# cpu.net
KiCad netlist of a schematic drawn in Altium Designer
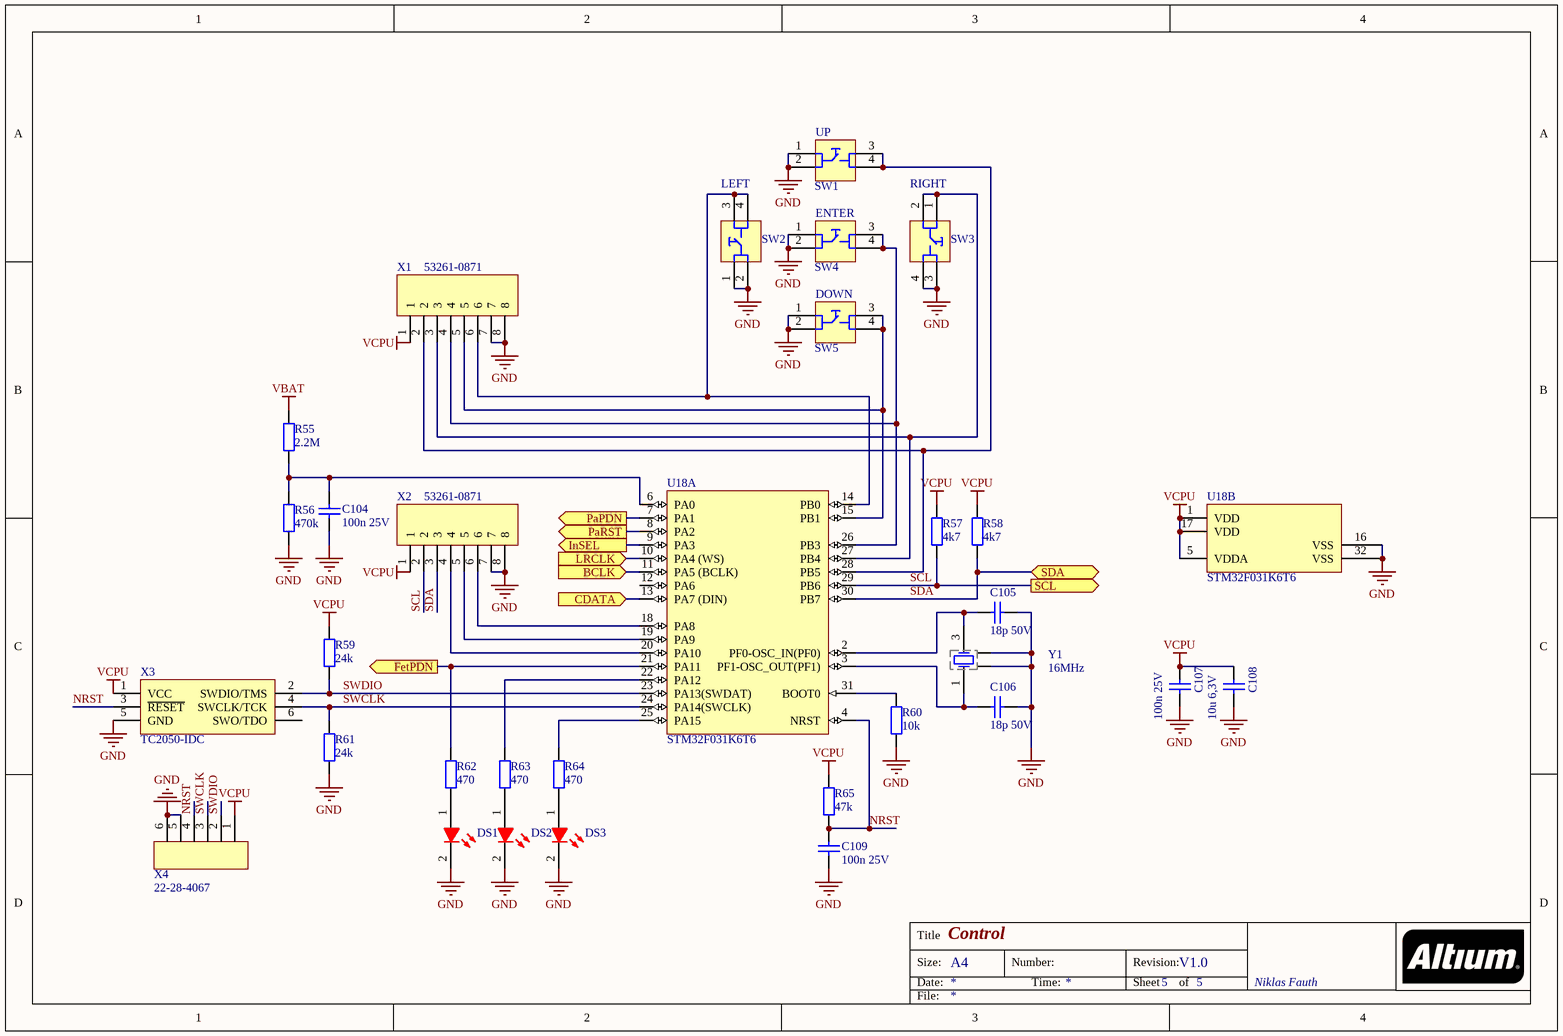
[diagram p0: cpu.SchDoc]

(export (version "E")
  (design (tool "Eeschema 10.0.6"))
  (components
    (comp (ref "C104")
      (value "100n 25V")
      (footprint "C-0603-H")
      (description "Capacitor 100n 25V")
      (libsource (lib "Passives") (part "C-0603-100n-25V"))
    )
    (comp (ref "C105")
      (value "18p 50V")
      (footprint "C-0402-M")
      (description "Capacitor 18p 50V")
      (libsource (lib "Passives") (part "C-0402-18p-50V"))
    )
    (comp (ref "C106")
      (value "18p 50V")
      (footprint "C-0402-M")
      (description "Capacitor 18p 50V")
      (libsource (lib "Passives") (part "C-0402-18p-50V"))
    )
    (comp (ref "C107")
      (value "100n 25V")
      (footprint "C-0603-H")
      (description "Capacitor 100n 25V")
      (libsource (lib "Passives") (part "C-0603-100n-25V"))
    )
    (comp (ref "C108")
      (value "10u 6,3V")
      (footprint "C-0603-H")
      (description "Capacitor 10uF 6,3V")
      (libsource (lib "Passives") (part "C-0603-10u-6,3V"))
    )
    (comp (ref "C109")
      (value "100n 25V")
      (footprint "C-0603-H")
      (description "Capacitor 100n 25V")
      (libsource (lib "Passives") (part "C-0603-100n-25V"))
    )
    (comp (ref "DS1")
      (value "LED-0603-RED")
      (footprint "LED-0603-RED")
      (libsource (lib "advanced") (part "LED-0603-RED"))
    )
    (comp (ref "DS2")
      (value "LED-0603-RED")
      (footprint "LED-0603-RED")
      (libsource (lib "advanced") (part "LED-0603-RED"))
    )
    (comp (ref "DS3")
      (value "LED-0603-RED")
      (footprint "LED-0603-RED")
      (libsource (lib "advanced") (part "LED-0603-RED"))
    )
    (comp (ref "R55")
      (value "2.2M")
      (footprint "R-0603-H")
      (description "Resistor 2.2M")
      (libsource (lib "Passives") (part "R-0603-2M2"))
    )
    (comp (ref "R56")
      (value "470k")
      (footprint "R-0603-H")
      (description "Resistor 470k")
      (libsource (lib "Passives") (part "R-0603-470k"))
    )
    (comp (ref "R57")
      (value "4k7")
      (footprint "R-0603-H")
      (description "Resistor 4k7")
      (libsource (lib "Passives") (part "R-0603-4k7"))
    )
    (comp (ref "R58")
      (value "4k7")
      (footprint "R-0603-H")
      (description "Resistor 4k7")
      (libsource (lib "Passives") (part "R-0603-4k7"))
    )
    (comp (ref "R59")
      (value "24k")
      (footprint "R-0402-M")
      (description "Resistor 24k")
      (libsource (lib "Passives") (part "R-0402-24k"))
    )
    (comp (ref "R60")
      (value "10k")
      (footprint "R-0603-H")
      (description "Resistor 10k")
      (libsource (lib "Passives") (part "R-0603-10k"))
    )
    (comp (ref "R61")
      (value "24k")
      (footprint "R-0402-M")
      (description "Resistor 24k")
      (libsource (lib "Passives") (part "R-0402-24k"))
    )
    (comp (ref "R62")
      (value "470")
      (footprint "R-0603-H")
      (description "Resistor 470")
      (libsource (lib "Passives") (part "R-0603-470"))
    )
    (comp (ref "R63")
      (value "470")
      (footprint "R-0603-H")
      (description "Resistor 470")
      (libsource (lib "Passives") (part "R-0603-470"))
    )
    (comp (ref "R64")
      (value "470")
      (footprint "R-0603-H")
      (description "Resistor 470")
      (libsource (lib "Passives") (part "R-0603-470"))
    )
    (comp (ref "R65")
      (value "47k")
      (footprint "R-0603-H")
      (description "Resistor 4k7")
      (libsource (lib "Passives") (part "R-0603-47k"))
    )
    (comp (ref "SW1") (value "UP") (footprint "BUTTON_TACT") (libsource (lib "") (part "SWITCH-TACTILE_1")))
    (comp (ref "SW2")
      (value "LEFT")
      (footprint "BUTTON_TACT")
      (libsource (lib "advanced") (part "SWITCH-TACTILE"))
    )
    (comp (ref "SW3")
      (value "RIGHT")
      (footprint "BUTTON_TACT")
      (libsource (lib "") (part "SWITCH-TACTILE_2"))
    )
    (comp (ref "SW4")
      (value "ENTER")
      (footprint "BUTTON_TACT")
      (libsource (lib "") (part "SWITCH-TACTILE_1"))
    )
    (comp (ref "SW5") (value "DOWN") (footprint "BUTTON_TACT") (libsource (lib "") (part "SWITCH-TACTILE_1")))
    (comp (ref "U18")
      (value "STM32F031K6T6")
      (footprint "LQFP32")
      (libsource (lib "advanced") (part "STM32F031K6T6"))
    )
    (comp (ref "X1")
      (value "53261-0871")
      (footprint "mlx-picoBlade-8p-right-SMD")
      (libsource (lib "advanced") (part "MLX-picoBlade-8P-right-SMD"))
    )
    (comp (ref "X2")
      (value "53261-0871")
      (footprint "mlx-picoBlade-8p-right-SMD")
      (libsource (lib "advanced") (part "MLX-picoBlade-8P-right-SMD"))
    )
    (comp (ref "X3")
      (value "TC2050-IDC")
      (footprint "TC2030-IDC")
      (description "TC2050-IDC SWD")
      (libsource (lib "advanced") (part "TAG-Connect-SWD"))
    )
    (comp (ref "X4")
      (value "22-28-4067")
      (footprint "PINHEAD-MALE-6")
      (libsource (lib "advanced") (part "PINHEAD-MALE-6"))
    )
    (comp (ref "Y1") (value "16MHz") (footprint "ABM10") (libsource (lib "advanced") (part "ABM10-16MHz")))
  )
  (nets
    (net (code "1") (name "/BCLK") (class "Default")
      (node (ref "U18") (pin "11") (pinfunction "PA5_(BCLK)_11") (pintype "bidirectional"))
    )
    (net (code "2") (name "/CDATA") (class "Default")
      (node (ref "U18") (pin "13") (pinfunction "PA7_(DIN)_13") (pintype "bidirectional"))
    )
    (net (code "3") (name "/FetPDN") (class "Default")
      (node (ref "R62") (pin "2") (pinfunction "2_2") (pintype "passive"))
      (node (ref "U18") (pin "21") (pinfunction "PA11_21") (pintype "bidirectional"))
    )
    (net (code "4") (name "/InSEL") (class "Default")
      (node (ref "U18") (pin "9") (pinfunction "PA3_9") (pintype "bidirectional"))
    )
    (net (code "5") (name "/LRCLK") (class "Default")
      (node (ref "U18") (pin "10") (pinfunction "PA4_(WS)_10") (pintype "bidirectional"))
    )
    (net (code "6") (name "/NRST") (class "Default")
      (node (ref "C109") (pin "2") (pinfunction "2_2") (pintype "passive"))
      (node (ref "R65") (pin "1") (pinfunction "1_1") (pintype "passive"))
      (node (ref "U18") (pin "4") (pinfunction "NRST_4") (pintype "bidirectional"))
      (node (ref "X3") (pin "3") (pinfunction "~{RESET}_3") (pintype "passive"))
      (node (ref "X4") (pin "4") (pintype "passive"))
    )
    (net (code "7") (name "/PaPDN") (class "Default")
      (node (ref "U18") (pin "7") (pinfunction "PA1_7") (pintype "bidirectional"))
    )
    (net (code "8") (name "/PaRST") (class "Default")
      (node (ref "U18") (pin "8") (pinfunction "PA2_8") (pintype "bidirectional"))
    )
    (net (code "9") (name "/SCL") (class "Default")
      (node (ref "R57") (pin "1") (pinfunction "1_1") (pintype "passive"))
      (node (ref "U18") (pin "29") (pinfunction "PB6_29") (pintype "bidirectional"))
      (node (ref "X2") (pin "2") (pinfunction "2_2") (pintype "passive"))
    )
    (net (code "10") (name "/SDA") (class "Default")
      (node (ref "R58") (pin "1") (pinfunction "1_1") (pintype "passive"))
      (node (ref "U18") (pin "30") (pinfunction "PB7_30") (pintype "bidirectional"))
      (node (ref "X2") (pin "3") (pinfunction "3_3") (pintype "passive"))
    )
    (net (code "11") (name "/SWCLK") (class "Default")
      (node (ref "R61") (pin "2") (pinfunction "2_2") (pintype "passive"))
      (node (ref "U18") (pin "24") (pinfunction "PA14(SWCLK)_24") (pintype "bidirectional"))
      (node (ref "X3") (pin "4") (pinfunction "SWCLK/TCK_4") (pintype "passive"))
      (node (ref "X4") (pin "3") (pintype "passive"))
    )
    (net (code "12") (name "/SWDIO") (class "Default")
      (node (ref "R59") (pin "1") (pinfunction "1_1") (pintype "passive"))
      (node (ref "U18") (pin "23") (pinfunction "PA13(SWDAT)_23") (pintype "bidirectional"))
      (node (ref "X3") (pin "2") (pinfunction "SWDIO/TMS_2") (pintype "passive"))
      (node (ref "X4") (pin "2") (pintype "passive"))
    )
    (net (code "13") (name "GND") (class "Default")
      (node (ref "C104") (pin "1") (pinfunction "1_1") (pintype "passive"))
      (node (ref "C105") (pin "2") (pinfunction "2_2") (pintype "passive"))
      (node (ref "C106") (pin "2") (pinfunction "2_2") (pintype "passive"))
      (node (ref "C107") (pin "1") (pinfunction "1_1") (pintype "passive"))
      (node (ref "C108") (pin "1") (pinfunction "1_1") (pintype "passive"))
      (node (ref "C109") (pin "1") (pinfunction "1_1") (pintype "passive"))
      (node (ref "DS1") (pin "2") (pinfunction "K_2") (pintype "passive"))
      (node (ref "DS2") (pin "2") (pinfunction "K_2") (pintype "passive"))
      (node (ref "DS3") (pin "2") (pinfunction "K_2") (pintype "passive"))
      (node (ref "R56") (pin "1") (pinfunction "1_1") (pintype "passive"))
      (node (ref "R60") (pin "1") (pinfunction "1_1") (pintype "passive"))
      (node (ref "R61") (pin "1") (pinfunction "1_1") (pintype "passive"))
      (node (ref "SW1") (pin "1") (pintype "passive"))
      (node (ref "SW1") (pin "2") (pintype "passive"))
      (node (ref "SW2") (pin "1") (pintype "passive"))
      (node (ref "SW2") (pin "2") (pintype "passive"))
      (node (ref "SW3") (pin "3") (pintype "passive"))
      (node (ref "SW3") (pin "4") (pintype "passive"))
      (node (ref "SW4") (pin "1") (pintype "passive"))
      (node (ref "SW4") (pin "2") (pintype "passive"))
      (node (ref "SW5") (pin "1") (pintype "passive"))
      (node (ref "SW5") (pin "2") (pintype "passive"))
      (node (ref "U18") (pin "16") (pinfunction "VSS_16") (pintype "passive"))
      (node (ref "U18") (pin "32") (pinfunction "VSS_32") (pintype "passive"))
      (node (ref "X1") (pin "7") (pinfunction "7_7") (pintype "power_in"))
      (node (ref "X1") (pin "8") (pinfunction "8_8") (pintype "power_in"))
      (node (ref "X2") (pin "7") (pinfunction "7_7") (pintype "power_in"))
      (node (ref "X2") (pin "8") (pinfunction "8_8") (pintype "power_in"))
      (node (ref "X3") (pin "5") (pinfunction "GND_5") (pintype "passive"))
      (node (ref "X4") (pin "5") (pinfunction "5_5") (pintype "passive"))
      (node (ref "X4") (pin "6") (pinfunction "6_6") (pintype "passive"))
      (node (ref "Y1") (pin "2") (pintype "power_in"))
      (node (ref "Y1") (pin "4") (pintype "power_in"))
    )
    (net (code "14") (name "Net-(DS1-A)") (class "Default")
      (node (ref "DS1") (pin "1") (pinfunction "A_1") (pintype "passive"))
      (node (ref "R62") (pin "1") (pinfunction "1_1") (pintype "passive"))
    )
    (net (code "15") (name "Net-(DS2-A)") (class "Default")
      (node (ref "DS2") (pin "1") (pinfunction "A_1") (pintype "passive"))
      (node (ref "R63") (pin "1") (pinfunction "1_1") (pintype "passive"))
    )
    (net (code "16") (name "Net-(DS3-A)") (class "Default")
      (node (ref "DS3") (pin "1") (pinfunction "A_1") (pintype "passive"))
      (node (ref "R64") (pin "1") (pinfunction "1_1") (pintype "passive"))
    )
    (net (code "17") (name "Net-(U18A-BOOT0)") (class "Default")
      (node (ref "R60") (pin "2") (pinfunction "2_2") (pintype "passive"))
      (node (ref "U18") (pin "31") (pinfunction "BOOT0_31") (pintype "input"))
    )
    (net (code "18") (name "Net-(U18A-PA0)") (class "Default")
      (node (ref "C104") (pin "2") (pinfunction "2_2") (pintype "passive"))
      (node (ref "R55") (pin "1") (pinfunction "1_1") (pintype "passive"))
      (node (ref "R56") (pin "2") (pinfunction "2_2") (pintype "passive"))
      (node (ref "U18") (pin "6") (pinfunction "PA0_6") (pintype "bidirectional"))
    )
    (net (code "19") (name "Net-(U18A-PA8)") (class "Default")
      (node (ref "U18") (pin "18") (pinfunction "PA8_18") (pintype "bidirectional"))
      (node (ref "X2") (pin "6") (pinfunction "6_6") (pintype "power_in"))
    )
    (net (code "20") (name "Net-(U18A-PA9)") (class "Default")
      (node (ref "U18") (pin "19") (pinfunction "PA9_19") (pintype "bidirectional"))
      (node (ref "X2") (pin "5") (pinfunction "5_5") (pintype "passive"))
    )
    (net (code "21") (name "Net-(U18A-PA10)") (class "Default")
      (node (ref "U18") (pin "20") (pinfunction "PA10_20") (pintype "bidirectional"))
      (node (ref "X2") (pin "4") (pinfunction "4_4") (pintype "passive"))
    )
    (net (code "22") (name "Net-(U18A-PA12)") (class "Default")
      (node (ref "R63") (pin "2") (pinfunction "2_2") (pintype "passive"))
      (node (ref "U18") (pin "22") (pinfunction "PA12_22") (pintype "bidirectional"))
    )
    (net (code "23") (name "Net-(U18A-PA15)") (class "Default")
      (node (ref "R64") (pin "2") (pinfunction "2_2") (pintype "passive"))
      (node (ref "U18") (pin "25") (pinfunction "PA15_25") (pintype "bidirectional"))
    )
    (net (code "24") (name "Net-(U18A-PB0)") (class "Default")
      (node (ref "SW2") (pin "3") (pintype "passive"))
      (node (ref "SW2") (pin "4") (pintype "passive"))
      (node (ref "U18") (pin "14") (pinfunction "PB0_14") (pintype "bidirectional"))
      (node (ref "X1") (pin "6") (pinfunction "6_6") (pintype "power_in"))
    )
    (net (code "25") (name "Net-(U18A-PB1)") (class "Default")
      (node (ref "SW5") (pin "3") (pintype "passive"))
      (node (ref "SW5") (pin "4") (pintype "passive"))
      (node (ref "U18") (pin "15") (pinfunction "PB1_15") (pintype "bidirectional"))
      (node (ref "X1") (pin "5") (pinfunction "5_5") (pintype "passive"))
    )
    (net (code "26") (name "Net-(U18A-PB3)") (class "Default")
      (node (ref "SW4") (pin "3") (pintype "passive"))
      (node (ref "SW4") (pin "4") (pintype "passive"))
      (node (ref "U18") (pin "26") (pinfunction "PB3_26") (pintype "bidirectional"))
      (node (ref "X1") (pin "4") (pinfunction "4_4") (pintype "passive"))
    )
    (net (code "27") (name "Net-(U18A-PB4)") (class "Default")
      (node (ref "SW3") (pin "1") (pintype "passive"))
      (node (ref "SW3") (pin "2") (pintype "passive"))
      (node (ref "U18") (pin "27") (pinfunction "PB4_27") (pintype "bidirectional"))
      (node (ref "X1") (pin "3") (pinfunction "3_3") (pintype "passive"))
    )
    (net (code "28") (name "Net-(U18A-PB5)") (class "Default")
      (node (ref "SW1") (pin "3") (pintype "passive"))
      (node (ref "SW1") (pin "4") (pintype "passive"))
      (node (ref "U18") (pin "28") (pinfunction "PB5_28") (pintype "bidirectional"))
      (node (ref "X1") (pin "2") (pinfunction "2_2") (pintype "passive"))
    )
    (net (code "29") (name "Net-(U18A-PF0-OSC_IN(PF0))") (class "Default")
      (node (ref "C105") (pin "1") (pinfunction "1_1") (pintype "passive"))
      (node (ref "U18") (pin "2") (pinfunction "PF0-OSC_IN(PF0)_2") (pintype "bidirectional"))
      (node (ref "Y1") (pin "3") (pintype "power_in"))
    )
    (net (code "30") (name "Net-(U18A-PF1-OSC_OUT(PF1))") (class "Default")
      (node (ref "C106") (pin "1") (pinfunction "1_1") (pintype "passive"))
      (node (ref "U18") (pin "3") (pinfunction "PF1-OSC_OUT(PF1)_3") (pintype "bidirectional"))
      (node (ref "Y1") (pin "1") (pintype "power_in"))
    )
    (net (code "31") (name "VBAT") (class "Default")
      (node (ref "R55") (pin "2") (pinfunction "2_2") (pintype "passive"))
    )
    (net (code "32") (name "VCPU") (class "Default")
      (node (ref "C107") (pin "2") (pinfunction "2_2") (pintype "passive"))
      (node (ref "C108") (pin "2") (pinfunction "2_2") (pintype "passive"))
      (node (ref "R57") (pin "2") (pinfunction "2_2") (pintype "passive"))
      (node (ref "R58") (pin "2") (pinfunction "2_2") (pintype "passive"))
      (node (ref "R59") (pin "2") (pinfunction "2_2") (pintype "passive"))
      (node (ref "R65") (pin "2") (pinfunction "2_2") (pintype "passive"))
      (node (ref "U18") (pin "1") (pinfunction "VDD_1") (pintype "power_in"))
      (node (ref "U18") (pin "17") (pinfunction "VDD_17") (pintype "power_in"))
      (node (ref "U18") (pin "5") (pinfunction "VDDA_5") (pintype "power_in"))
      (node (ref "X1") (pin "1") (pinfunction "1_1") (pintype "passive"))
      (node (ref "X2") (pin "1") (pinfunction "1_1") (pintype "passive"))
      (node (ref "X3") (pin "1") (pinfunction "VCC_1") (pintype "passive"))
      (node (ref "X4") (pin "1") (pintype "passive"))
    )
    (net (code "33") (name "unconnected-(U18A-PA6-Pad12)") (class "Default")
      (node (ref "U18") (pin "12") (pinfunction "PA6_12") (pintype "bidirectional"))
    )
    (net (code "34") (name "unconnected-(X3-SWO{slash}TDO-Pad6)") (class "Default")
      (node (ref "X3") (pin "6") (pinfunction "SWO/TDO_6") (pintype "passive"))
    )
  )
)
